# 5V0_SYS_SUPPLY.net
KiCad netlist of a schematic drawn in Altium Designer
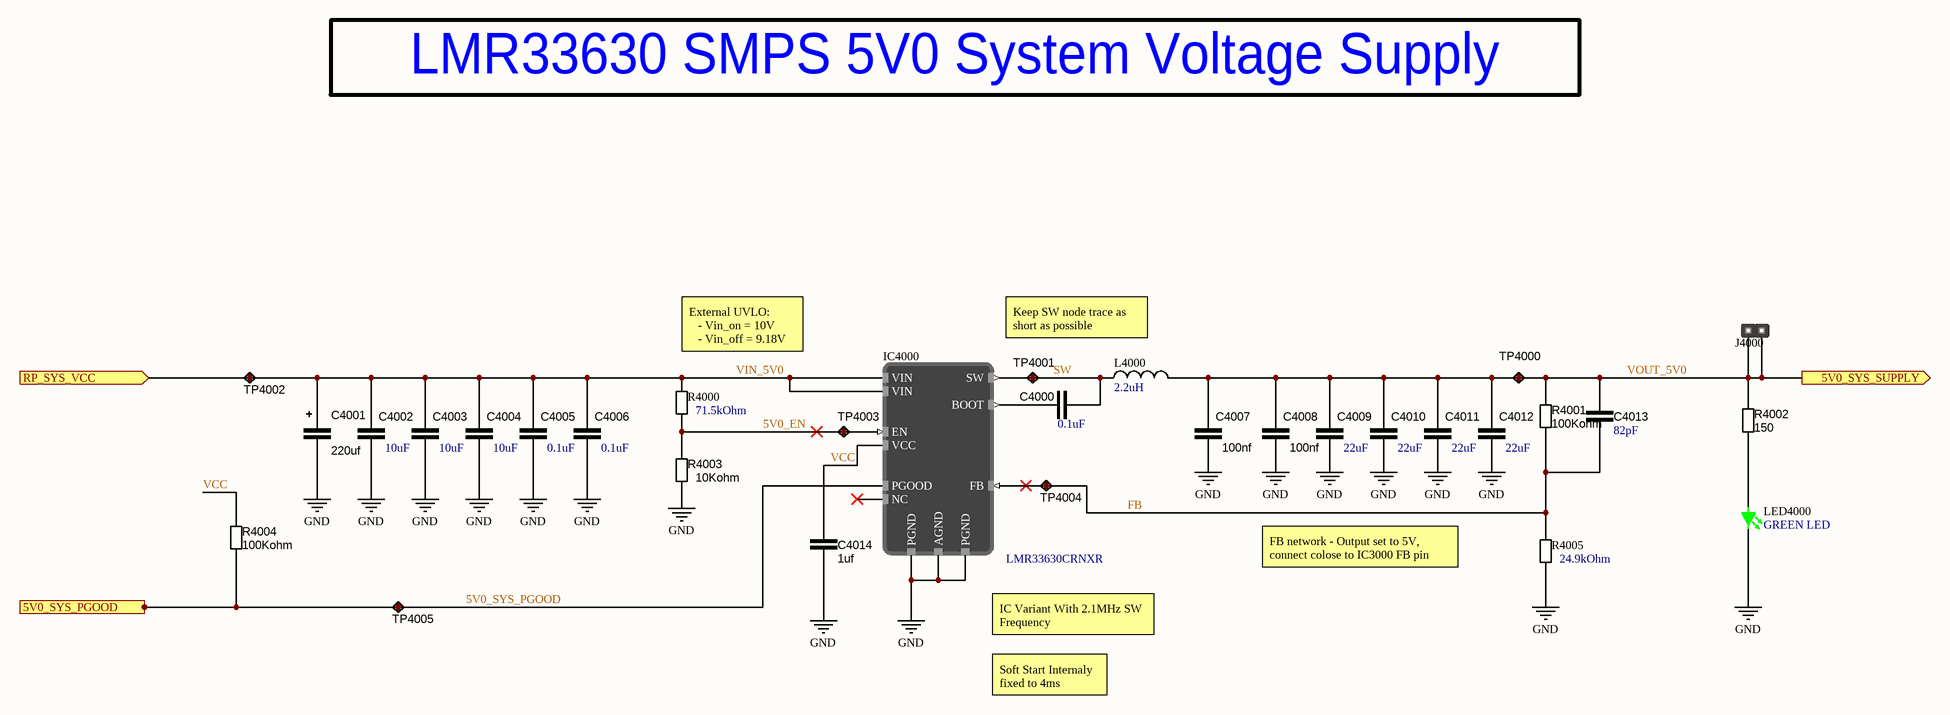
[diagram p0: 5V0_SYS_SUPPLY.SchDoc]

(export (version "E")
  (design (tool "Eeschema 10.0.6"))
  (components
    (comp (ref "C4000")
      (value "0.1uF")
      (footprint "CAP_0603")
      (description "CAP CER 0.1UF 50V X7R 0603")
      (fields (field (name "DIGIKEY PART NUMBER") "1276-1000-1-ND"))
      (libsource (lib "") (part "C000018_1"))
    )
    (comp (ref "C4001")
      (value "220uf")
      (footprint "CAPAE109103X103M")
      (description "CAP ALUM 220UF 20% 50V SMD")
      (fields (field (name "DIGIKEY PART NUMBER") "493-9426-1-ND"))
      (libsource (lib "CapacitorsIntegrated") (part "C000019"))
    )
    (comp (ref "C4002")
      (value "10uF")
      (footprint "CAP_1206")
      (description "CAP CER 10UF 50V X7R 1206")
      (fields (field (name "DIGIKEY PART NUMBER") "1276-6767-1-ND"))
      (libsource (lib "CapacitorsIntegrated") (part "C000017"))
    )
    (comp (ref "C4003")
      (value "10uF")
      (footprint "CAP_1206")
      (description "CAP CER 10UF 50V X7R 1206")
      (fields (field (name "DIGIKEY PART NUMBER") "1276-6767-1-ND"))
      (libsource (lib "CapacitorsIntegrated") (part "C000017"))
    )
    (comp (ref "C4004")
      (value "10uF")
      (footprint "CAP_1206")
      (description "CAP CER 10UF 50V X7R 1206")
      (fields (field (name "DIGIKEY PART NUMBER") "1276-6767-1-ND"))
      (libsource (lib "CapacitorsIntegrated") (part "C000017"))
    )
    (comp (ref "C4005")
      (value "0.1uF")
      (footprint "CAP_0603")
      (description "CAP CER 0.1UF 50V X7R 0603")
      (fields (field (name "DIGIKEY PART NUMBER") "1276-1000-1-ND"))
      (libsource (lib "CapacitorsIntegrated") (part "C000018"))
    )
    (comp (ref "C4006")
      (value "0.1uF")
      (footprint "CAP_0603")
      (description "CAP CER 0.1UF 50V X7R 0603")
      (fields (field (name "DIGIKEY PART NUMBER") "1276-1000-1-ND"))
      (libsource (lib "CapacitorsIntegrated") (part "C000018"))
    )
    (comp (ref "C4007")
      (value "100nf")
      (footprint "CAP_0603")
      (description "CAP CER 100nF 0603 25V X7R")
      (libsource (lib "CapacitorsIntegrated") (part "C000007"))
    )
    (comp (ref "C4008")
      (value "100nf")
      (footprint "CAP_0603")
      (description "CAP CER 100nF 0603 25V X7R")
      (libsource (lib "CapacitorsIntegrated") (part "C000007"))
    )
    (comp (ref "C4009")
      (value "22uF")
      (footprint "CAP_1206")
      (description "22 µF ±10% 25V Ceramic Capacitor X5R 1206 (3216 Metric)")
      (fields (field (name "DIGIKEY PART NUMBER") "1276-3047-1-ND"))
      (libsource (lib "CapacitorsIntegrated") (part "C000020"))
    )
    (comp (ref "C4010")
      (value "22uF")
      (footprint "CAP_1206")
      (description "22 µF ±10% 25V Ceramic Capacitor X5R 1206 (3216 Metric)")
      (fields (field (name "DIGIKEY PART NUMBER") "1276-3047-1-ND"))
      (libsource (lib "CapacitorsIntegrated") (part "C000020"))
    )
    (comp (ref "C4011")
      (value "22uF")
      (footprint "CAP_1206")
      (description "22 µF ±10% 25V Ceramic Capacitor X5R 1206 (3216 Metric)")
      (fields (field (name "DIGIKEY PART NUMBER") "1276-3047-1-ND"))
      (libsource (lib "CapacitorsIntegrated") (part "C000020"))
    )
    (comp (ref "C4012")
      (value "22uF")
      (footprint "CAP_1206")
      (description "22 µF ±10% 25V Ceramic Capacitor X5R 1206 (3216 Metric)")
      (fields (field (name "DIGIKEY PART NUMBER") "1276-3047-1-ND"))
      (libsource (lib "CapacitorsIntegrated") (part "C000020"))
    )
    (comp (ref "C4013")
      (value "82pF")
      (footprint "CAP_0603")
      (description "82 pF ±1% 25V Ceramic Capacitor C0G, NP0 0603 (1608 Metric)")
      (fields (field (name "DIGIKEY PART NUMBER") "478-KGM15ACG1E820FTCT-ND"))
      (libsource (lib "CapacitorsIntegrated") (part "C000021"))
    )
    (comp (ref "C4014")
      (value "1uf")
      (footprint "CAP_0603")
      (description "CAP CER 1uF 10V X7R 0603")
      (fields (field (name "DIGIKEY PART NUMBER") "1276-1946-2-ND"))
      (libsource (lib "CapacitorsIntegrated") (part "C000011"))
    )
    (comp (ref "IC4000")
      (value "LMR33630CRNXR")
      (footprint "VQFN-HR")
      (description "Buck Switching Regulator IC Positive Adjustable 1V 1 Output 3A 12-PowerVFQFN")
      (fields
        (field (name "DIGIKEY PART NUMBER") "296-49768-1-ND")
        (field (name "MOUSER PART NUMBER") "595-LMR33630CRNXR")
      )
      (libsource (lib "IntegratedCircuits") (part "LMR33630CRNXR"))
    )
    (comp (ref "J4000") (value "*") (footprint "HM1x2") (libsource (lib "motion_board") (part "HEADER_1x2")))
    (comp (ref "L4000")
      (value "2.2uH")
      (footprint "InductorsFootprint:INDP_518X518")
      (description "FIXED IND 2.2UH 4.2A 50.1MOHM SM")
      (fields (field (name "DIGIKEY PART NUMBER") "541-1088-1-ND"))
      (libsource (lib "Inductors") (part "L000012"))
    )
    (comp (ref "LED4000")
      (value "GREEN LED")
      (footprint "DIOC1608X04N")
      (description "LED GREEN DIFFUSED 0603 SMD")
      (libsource (lib "Miscellaneous_Lib1") (part "00000001"))
    )
    (comp (ref "R4000")
      (value "71.5kOhm")
      (footprint "RES_0603")
      (description "71.5 kOhms ±1% 0.1W, 1/10W Chip Resistor 0603 (1608 Metric) Moisture Resistant Thick Film")
      (fields (field (name "DIGIKEY PART NUMBER") "311-71.5KHRCT-ND"))
      (libsource (lib "ResistorsIntegrated") (part "R000022"))
    )
    (comp (ref "R4001")
      (value "100Kohm")
      (footprint "RES_0603")
      (description "RES 100K OHM 1% 1/10W 0603")
      (libsource (lib "ResistorsIntegrated") (part "R000006"))
    )
    (comp (ref "R4002")
      (value "150")
      (footprint "RES_0603")
      (description "RES 150 OHM 1% 1/10W 0603")
      (libsource (lib "ResistorsIntegrated") (part "R000004"))
    )
    (comp (ref "R4003")
      (value "10Kohm")
      (footprint "RES_0603")
      (description "RES 10K OHM 1% 1/10W 0603")
      (libsource (lib "ResistorsIntegrated") (part "R000001"))
    )
    (comp (ref "R4004")
      (value "100Kohm")
      (footprint "RES_0603")
      (description "RES 100K OHM 1% 1/10W 0603")
      (libsource (lib "ResistorsIntegrated") (part "R000006"))
    )
    (comp (ref "R4005")
      (value "24.9kOhm")
      (footprint "RES_0603")
      (description "24.9 kOhms ±1% 0.1W, 1/10W Chip Resistor 0603 (1608 Metric) Automotive AEC-Q200 Thick Film")
      (fields (field (name "DIGIKEY PART NUMBER") "P24.9KHCT-ND"))
      (libsource (lib "ResistorsIntegrated") (part "R000017"))
    )
    (comp (ref "TP4000")
      (value "Test point")
      (footprint "TestPoint")
      (description "Test point 1mm")
      (libsource (lib "IntegratedCircuits") (part "TP002"))
    )
    (comp (ref "TP4001")
      (value "Test point")
      (footprint "TestPoint")
      (description "Test point 1mm")
      (libsource (lib "IntegratedCircuits") (part "TP002"))
    )
    (comp (ref "TP4002")
      (value "Test point")
      (footprint "TestPoint")
      (description "Test point 1mm")
      (libsource (lib "IntegratedCircuits") (part "TP002"))
    )
    (comp (ref "TP4003")
      (value "Test point")
      (footprint "TestPoint")
      (description "Test point 1mm")
      (libsource (lib "IntegratedCircuits") (part "TP002"))
    )
    (comp (ref "TP4004")
      (value "Test point")
      (footprint "TestPoint")
      (description "Test point 1mm")
      (libsource (lib "IntegratedCircuits") (part "TP002"))
    )
    (comp (ref "TP4005")
      (value "Test point")
      (footprint "TestPoint")
      (description "Test point 1mm")
      (libsource (lib "IntegratedCircuits") (part "TP002"))
    )
  )
  (nets
    (net (code "1") (name "/5V0_EN") (class "Default")
      (node (ref "IC4000") (pin "9") (pinfunction "EN_9") (pintype "input"))
      (node (ref "R4000") (pin "1") (pinfunction "1_1") (pintype "passive"))
      (node (ref "R4003") (pin "2") (pinfunction "2_2") (pintype "passive"))
      (node (ref "TP4003") (pin "1") (pinfunction "1_1") (pintype "passive"))
    )
    (net (code "2") (name "/5V0_SYS_PGOOD") (class "Default")
      (node (ref "IC4000") (pin "8") (pinfunction "PGOOD_8") (pintype "open_collector"))
      (node (ref "R4004") (pin "1") (pinfunction "1_1") (pintype "passive"))
      (node (ref "TP4005") (pin "1") (pinfunction "1_1") (pintype "passive"))
    )
    (net (code "3") (name "/FB") (class "Default")
      (node (ref "C4013") (pin "1") (pinfunction "1_1") (pintype "passive"))
      (node (ref "IC4000") (pin "7") (pinfunction "FB_7") (pintype "input"))
      (node (ref "R4001") (pin "1") (pinfunction "1_1") (pintype "passive"))
      (node (ref "R4005") (pin "2") (pinfunction "2_2") (pintype "passive"))
      (node (ref "TP4004") (pin "1") (pinfunction "1_1") (pintype "passive"))
    )
    (net (code "4") (name "/SW") (class "Default")
      (node (ref "C4000") (pin "2") (pinfunction "2_2") (pintype "passive"))
      (node (ref "IC4000") (pin "12") (pinfunction "SW_12") (pintype "output"))
      (node (ref "L4000") (pin "1") (pinfunction "1_1") (pintype "passive"))
      (node (ref "TP4001") (pin "1") (pinfunction "1_1") (pintype "passive"))
    )
    (net (code "5") (name "/VCC") (class "Default")
      (node (ref "C4014") (pin "2") (pinfunction "2_2") (pintype "passive"))
      (node (ref "IC4000") (pin "5") (pinfunction "VCC_5") (pintype "power_in"))
      (node (ref "R4004") (pin "2") (pinfunction "2_2") (pintype "passive"))
    )
    (net (code "6") (name "/VIN_5V0") (class "Default")
      (node (ref "C4001") (pin "2") (pinfunction "2_2") (pintype "passive"))
      (node (ref "C4002") (pin "2") (pinfunction "2_2") (pintype "passive"))
      (node (ref "C4003") (pin "2") (pinfunction "2_2") (pintype "passive"))
      (node (ref "C4004") (pin "2") (pinfunction "2_2") (pintype "passive"))
      (node (ref "C4005") (pin "2") (pinfunction "2_2") (pintype "passive"))
      (node (ref "C4006") (pin "2") (pinfunction "2_2") (pintype "passive"))
      (node (ref "IC4000") (pin "10") (pinfunction "VIN_10") (pintype "passive"))
      (node (ref "IC4000") (pin "2") (pinfunction "VIN_2") (pintype "passive"))
      (node (ref "R4000") (pin "2") (pinfunction "2_2") (pintype "passive"))
      (node (ref "TP4002") (pin "1") (pinfunction "1_1") (pintype "passive"))
    )
    (net (code "7") (name "/VOUT_5V0") (class "Default")
      (node (ref "C4007") (pin "2") (pinfunction "2_2") (pintype "passive"))
      (node (ref "C4008") (pin "2") (pinfunction "2_2") (pintype "passive"))
      (node (ref "C4009") (pin "2") (pinfunction "2_2") (pintype "passive"))
      (node (ref "C4010") (pin "2") (pinfunction "2_2") (pintype "passive"))
      (node (ref "C4011") (pin "2") (pinfunction "2_2") (pintype "passive"))
      (node (ref "C4012") (pin "2") (pinfunction "2_2") (pintype "passive"))
      (node (ref "C4013") (pin "2") (pinfunction "2_2") (pintype "passive"))
      (node (ref "J4000") (pin "1") (pinfunction "1_1") (pintype "passive"))
      (node (ref "J4000") (pin "2") (pinfunction "1_2") (pintype "passive"))
      (node (ref "L4000") (pin "2") (pinfunction "2_2") (pintype "passive"))
      (node (ref "R4001") (pin "2") (pinfunction "2_2") (pintype "passive"))
      (node (ref "R4002") (pin "2") (pinfunction "2_2") (pintype "passive"))
      (node (ref "TP4000") (pin "1") (pinfunction "1_1") (pintype "passive"))
    )
    (net (code "8") (name "GND") (class "Default")
      (node (ref "C4001") (pin "1") (pinfunction "1_1") (pintype "passive"))
      (node (ref "C4002") (pin "1") (pinfunction "1_1") (pintype "passive"))
      (node (ref "C4003") (pin "1") (pinfunction "1_1") (pintype "passive"))
      (node (ref "C4004") (pin "1") (pinfunction "1_1") (pintype "passive"))
      (node (ref "C4005") (pin "1") (pinfunction "1_1") (pintype "passive"))
      (node (ref "C4006") (pin "1") (pinfunction "1_1") (pintype "passive"))
      (node (ref "C4007") (pin "1") (pinfunction "1_1") (pintype "passive"))
      (node (ref "C4008") (pin "1") (pinfunction "1_1") (pintype "passive"))
      (node (ref "C4009") (pin "1") (pinfunction "1_1") (pintype "passive"))
      (node (ref "C4010") (pin "1") (pinfunction "1_1") (pintype "passive"))
      (node (ref "C4011") (pin "1") (pinfunction "1_1") (pintype "passive"))
      (node (ref "C4012") (pin "1") (pinfunction "1_1") (pintype "passive"))
      (node (ref "C4014") (pin "1") (pinfunction "1_1") (pintype "passive"))
      (node (ref "IC4000") (pin "1") (pinfunction "PGND_1") (pintype "power_in"))
      (node (ref "IC4000") (pin "11") (pinfunction "PGND_11") (pintype "power_in"))
      (node (ref "IC4000") (pin "6") (pinfunction "AGND_6") (pintype "power_in"))
      (node (ref "LED4000") (pin "2") (pinfunction "2_2") (pintype "passive"))
      (node (ref "R4003") (pin "1") (pinfunction "1_1") (pintype "passive"))
      (node (ref "R4005") (pin "1") (pinfunction "1_1") (pintype "passive"))
    )
    (net (code "9") (name "Net-(IC4000-BOOT)") (class "Default")
      (node (ref "C4000") (pin "1") (pinfunction "1_1") (pintype "passive"))
      (node (ref "IC4000") (pin "4") (pinfunction "BOOT_4") (pintype "output"))
    )
    (net (code "10") (name "Net-(LED4000-Pad1)") (class "Default")
      (node (ref "LED4000") (pin "1") (pinfunction "1_1") (pintype "passive"))
      (node (ref "R4002") (pin "1") (pinfunction "1_1") (pintype "passive"))
    )
    (net (code "11") (name "unconnected-(IC4000-NC-Pad3)") (class "Default")
      (node (ref "IC4000") (pin "3") (pinfunction "NC_3") (pintype "tri_state+no_connect"))
    )
  )
)
